# Thetis_RevF1_SCH.net
KiCad netlist of a schematic drawn in EAGLE
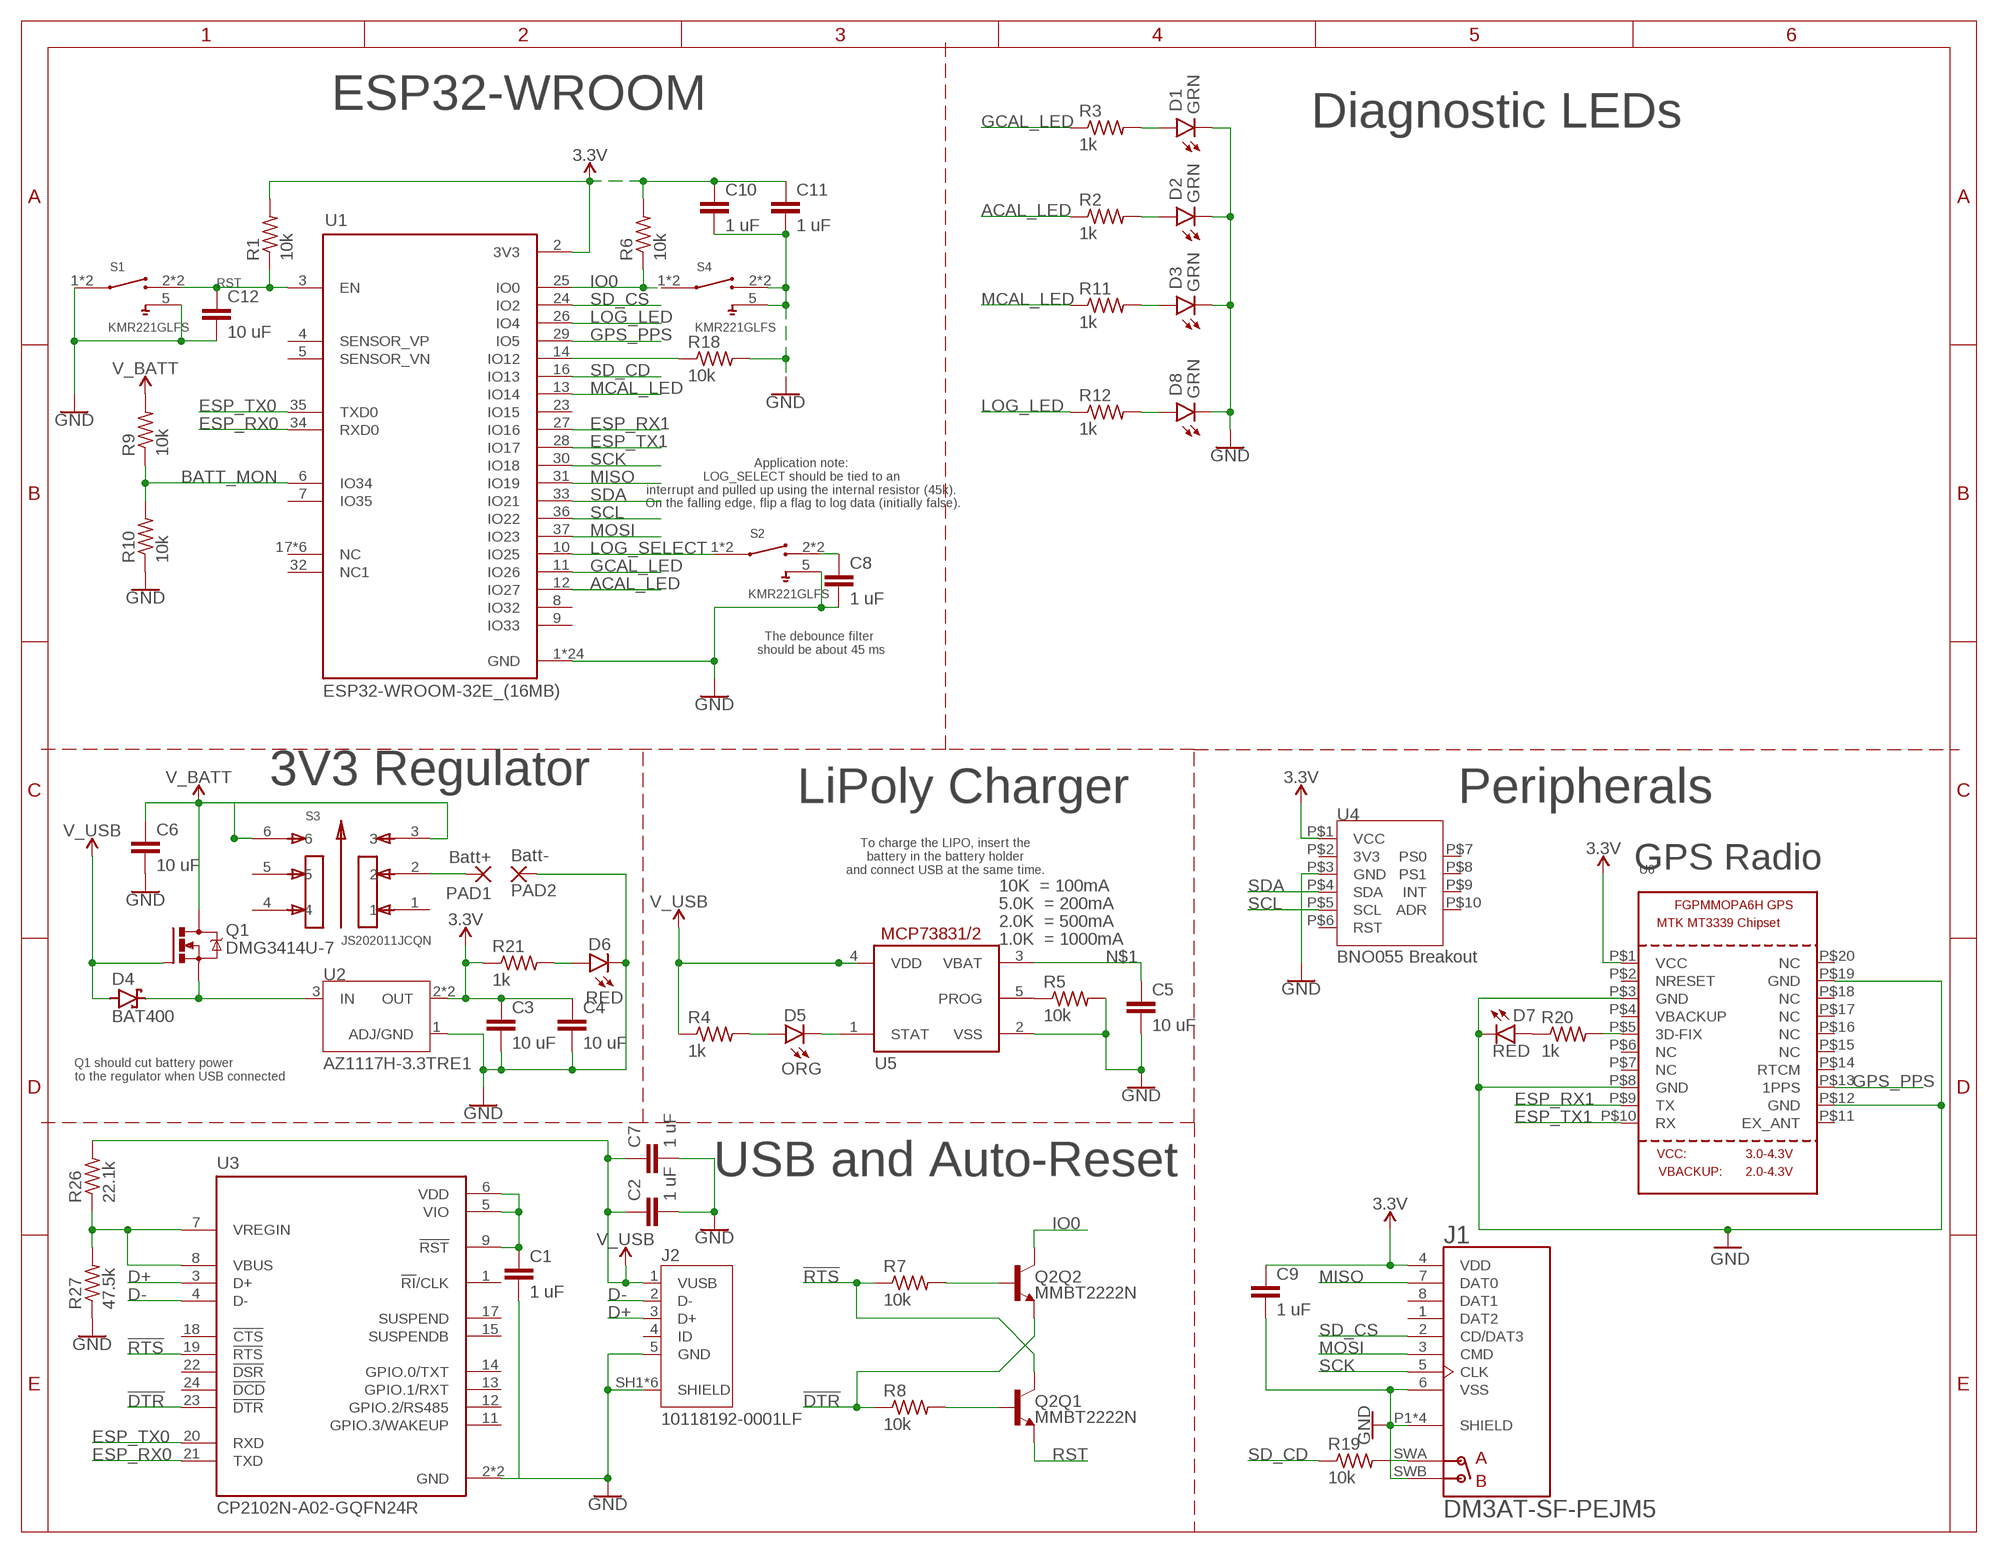
[diagram p0: schematic, sheet 1]

(export (version "E")
  (design (tool "Eeschema 10.0.6"))
  (components
    (comp (ref "C1")
      (value "1 uF")
      (footprint "eagle-import:C0603")
      (libsource (lib "eagle-import") (part "C-EUC0603"))
    )
    (comp (ref "C2")
      (value "1 uF")
      (footprint "eagle-import:C0603")
      (libsource (lib "eagle-import") (part "C-EUC0603"))
    )
    (comp (ref "C3")
      (value "10 uF")
      (footprint "eagle-import:C0603")
      (libsource (lib "eagle-import") (part "C-EUC0603"))
    )
    (comp (ref "C4")
      (value "10 uF")
      (footprint "eagle-import:C0603")
      (libsource (lib "eagle-import") (part "C-EUC0603"))
    )
    (comp (ref "C5")
      (value "10 uF")
      (footprint "eagle-import:C0603")
      (libsource (lib "eagle-import") (part "C-EUC0603"))
    )
    (comp (ref "C6")
      (value "10 uF")
      (footprint "eagle-import:C0603")
      (libsource (lib "eagle-import") (part "C-EUC0603"))
    )
    (comp (ref "C7")
      (value "1 uF")
      (footprint "eagle-import:C0603")
      (libsource (lib "eagle-import") (part "C-EUC0603"))
    )
    (comp (ref "C8")
      (value "1 uF")
      (footprint "eagle-import:C0603")
      (libsource (lib "eagle-import") (part "C-EUC0603"))
    )
    (comp (ref "C9")
      (value "1 uF")
      (footprint "eagle-import:C0603")
      (libsource (lib "eagle-import") (part "C-EUC0603"))
    )
    (comp (ref "C10")
      (value "1 uF")
      (footprint "eagle-import:C0603")
      (libsource (lib "eagle-import") (part "C-EUC0603"))
    )
    (comp (ref "C11")
      (value "1 uF")
      (footprint "eagle-import:C0603")
      (libsource (lib "eagle-import") (part "C-EUC0603"))
    )
    (comp (ref "C12")
      (value "10 uF")
      (footprint "eagle-import:C0603")
      (libsource (lib "eagle-import") (part "C-EUC0603"))
    )
    (comp (ref "D1")
      (value "GRN")
      (footprint "eagle-import:LEDC1608X65N")
      (libsource (lib "eagle-import") (part "CHIP-ROUND-G_0603"))
    )
    (comp (ref "D2")
      (value "GRN")
      (footprint "eagle-import:LEDC1608X65N")
      (libsource (lib "eagle-import") (part "CHIP-ROUND-G_0603"))
    )
    (comp (ref "D3")
      (value "GRN")
      (footprint "eagle-import:LEDC1608X65N")
      (libsource (lib "eagle-import") (part "CHIP-ROUND-G_0603"))
    )
    (comp (ref "D4")
      (value "BAT400")
      (footprint "eagle-import:SOT23")
      (libsource (lib "eagle-import") (part "BAS40"))
    )
    (comp (ref "D5")
      (value "ORG")
      (footprint "eagle-import:LEDC1608X65N")
      (libsource (lib "eagle-import") (part "CHIP-ROUND-G_0603"))
    )
    (comp (ref "D6")
      (value "RED")
      (footprint "eagle-import:LEDC1608X65N")
      (libsource (lib "eagle-import") (part "CHIP-ROUND-G_0603"))
    )
    (comp (ref "D7")
      (value "RED")
      (footprint "eagle-import:LEDC1608X35N")
      (libsource (lib "eagle-import") (part "CHIP-FLAT-Y_0603-0.35MM"))
    )
    (comp (ref "D8")
      (value "GRN")
      (footprint "eagle-import:LEDC1608X65N")
      (libsource (lib "eagle-import") (part "CHIP-ROUND-G_0603"))
    )
    (comp (ref "J1")
      (value "DM3AT-SF-PEJM5")
      (footprint "eagle-import:HRS_DM3AT-SF-PEJM5")
      (fields (field (name "MF") "Hirose"))
      (libsource (lib "eagle-import") (part "DM3AT-SF-PEJM5"))
    )
    (comp (ref "J2")
      (value "10118192-0001LF")
      (footprint "eagle-import:AMPHENOL_10118192-0001LF")
      (fields (field (name "MANUFACTURER") "Amphenol"))
      (libsource (lib "eagle-import") (part "10118192-0001LF"))
    )
    (comp (ref "PAD1")
      (value "Batt+")
      (footprint "eagle-import:SMD2,54-5,08")
      (libsource (lib "eagle-import") (part "SMD5"))
    )
    (comp (ref "PAD2")
      (value "Batt-")
      (footprint "eagle-import:SMD2,54-5,08")
      (libsource (lib "eagle-import") (part "SMD5"))
    )
    (comp (ref "Q1")
      (value "DMG3414U-7")
      (footprint "eagle-import:SOT23")
      (libsource (lib "eagle-import") (part "NMOSFETSOT23"))
    )
    (comp (ref "Q2")
      (value "MMBT2222N")
      (footprint "eagle-import:SC70-6")
      (libsource (lib "eagle-import") (part "TRANS_NPN_DUAL-MBT3904DW1T1"))
    )
    (comp (ref "R1")
      (value "10k")
      (footprint "eagle-import:R0603")
      (libsource (lib "eagle-import") (part "R-US_R0603"))
    )
    (comp (ref "R2")
      (value "1k")
      (footprint "eagle-import:R0603")
      (libsource (lib "eagle-import") (part "R-US_R0603"))
    )
    (comp (ref "R3")
      (value "1k")
      (footprint "eagle-import:R0603")
      (libsource (lib "eagle-import") (part "R-US_R0603"))
    )
    (comp (ref "R4")
      (value "1k")
      (footprint "eagle-import:R0603")
      (libsource (lib "eagle-import") (part "R-US_R0603"))
    )
    (comp (ref "R5")
      (value "10k")
      (footprint "eagle-import:R0603")
      (libsource (lib "eagle-import") (part "R-US_R0603"))
    )
    (comp (ref "R6")
      (value "10k")
      (footprint "eagle-import:R0603")
      (libsource (lib "eagle-import") (part "R-US_R0603"))
    )
    (comp (ref "R7")
      (value "10k")
      (footprint "eagle-import:R0603")
      (libsource (lib "eagle-import") (part "R-US_R0603"))
    )
    (comp (ref "R8")
      (value "10k")
      (footprint "eagle-import:R0603")
      (libsource (lib "eagle-import") (part "R-US_R0603"))
    )
    (comp (ref "R9")
      (value "10k")
      (footprint "eagle-import:R0603")
      (libsource (lib "eagle-import") (part "R-US_R0603"))
    )
    (comp (ref "R10")
      (value "10k")
      (footprint "eagle-import:R0603")
      (libsource (lib "eagle-import") (part "R-US_R0603"))
    )
    (comp (ref "R11")
      (value "1k")
      (footprint "eagle-import:R0603")
      (libsource (lib "eagle-import") (part "R-US_R0603"))
    )
    (comp (ref "R12")
      (value "1k")
      (footprint "eagle-import:R0603")
      (libsource (lib "eagle-import") (part "R-US_R0603"))
    )
    (comp (ref "R18")
      (value "10k")
      (footprint "eagle-import:R0603")
      (libsource (lib "eagle-import") (part "R-US_R0603"))
    )
    (comp (ref "R19")
      (value "10k")
      (footprint "eagle-import:R0603")
      (libsource (lib "eagle-import") (part "R-US_R0603"))
    )
    (comp (ref "R20")
      (value "1k")
      (footprint "eagle-import:R0603")
      (libsource (lib "eagle-import") (part "R-US_R0603"))
    )
    (comp (ref "R21")
      (value "1k")
      (footprint "eagle-import:R0603")
      (libsource (lib "eagle-import") (part "R-US_R0603"))
    )
    (comp (ref "R26")
      (value "22.1k")
      (footprint "eagle-import:R0603")
      (libsource (lib "eagle-import") (part "R-US_R0603"))
    )
    (comp (ref "R27")
      (value "47.5k")
      (footprint "eagle-import:R0603")
      (libsource (lib "eagle-import") (part "R-US_R0603"))
    )
    (comp (ref "S1")
      (value "KMR221GLFS")
      (footprint "eagle-import:SW_KMR221GLFS")
      (fields (field (name "MANUFACTURER") "CnK"))
      (libsource (lib "eagle-import") (part "KMR221GLFS"))
    )
    (comp (ref "S2")
      (value "KMR221GLFS")
      (footprint "eagle-import:SW_KMR221GLFS")
      (fields (field (name "MANUFACTURER") "CnK"))
      (libsource (lib "eagle-import") (part "KMR221GLFS"))
    )
    (comp (ref "S3")
      (value "JS202011JCQN")
      (footprint "eagle-import:SW_JS202011JCQN")
      (libsource (lib "eagle-import") (part "JS202011JCQN"))
    )
    (comp (ref "S4")
      (value "KMR221GLFS")
      (footprint "eagle-import:SW_KMR221GLFS")
      (fields (field (name "MANUFACTURER") "CnK"))
      (libsource (lib "eagle-import") (part "KMR221GLFS"))
    )
    (comp (ref "U1")
      (value "ESP32-WROOM-32E_(16MB)")
      (footprint "eagle-import:MODULE_ESP32-WROOM-32E_(16MB)")
      (fields (field (name "MANUFACTURER") "Espressif Systems"))
      (libsource (lib "eagle-import") (part "ESP32-WROOM-32E_(16MB)"))
    )
    (comp (ref "U2")
      (value "AZ1117H-3.3TRE1")
      (footprint "eagle-import:SOT230P700X180-4N")
      (fields (field (name "MF") "Diodes Inc.") (field (name "MP") "AZ1117EH-5.0TRG1"))
      (libsource (lib "eagle-import") (part "AZ1117EH-5.0TRG1"))
    )
    (comp (ref "U3")
      (value "CP2102N-A02-GQFN24R")
      (footprint "eagle-import:QFN50P400X400X80-25N")
      (fields (field (name "MANUFACTURER") "Silicon Labs"))
      (libsource (lib "eagle-import") (part "CP2102N-A02-GQFN24R"))
    )
    (comp (ref "U4")
      (value "BNO055 Breakout")
      (footprint "eagle-import:ADAFRUIT-BNO055-BREAKOUT-SMD")
      (libsource (lib "eagle-import") (part "ADAFRUIT-BNO055-BREAKOUT-SMD"))
    )
    (comp (ref "U5")
      (value "MCP73831/OT")
      (footprint "eagle-import:SOT23-5L")
      (libsource (lib "eagle-import") (part "MCP73831/OT"))
    )
    (comp (ref "U6")
      (value "GPS_FGPMMOPA6H")
      (footprint "eagle-import:FGPMMOPA6H")
      (libsource (lib "eagle-import") (part "GPS_FGPMMOPA6H"))
    )
  )
  (nets
    (net (code "1") (name "/3V3") (class "Default")
      (node (ref "U4") (pin "P$2") (pinfunction "3V3_P$2") (pintype "power_in"))
    )
    (net (code "2") (name "/ACAL_LED") (class "Default")
      (node (ref "R2") (pin "1") (pinfunction "1_1") (pintype "passive"))
      (node (ref "U1") (pin "12") (pinfunction "IO27_12") (pintype "bidirectional"))
    )
    (net (code "3") (name "/BATT_MON") (class "Default")
      (node (ref "R10") (pin "2") (pinfunction "2_2") (pintype "passive"))
      (node (ref "R9") (pin "1") (pinfunction "1_1") (pintype "passive"))
      (node (ref "U1") (pin "6") (pinfunction "IO34_6") (pintype "input"))
    )
    (net (code "4") (name "/D+") (class "Default")
      (node (ref "J2") (pin "3") (pinfunction "D+_3") (pintype "passive"))
      (node (ref "U3") (pin "3") (pinfunction "D+_3") (pintype "bidirectional"))
    )
    (net (code "5") (name "/D-") (class "Default")
      (node (ref "J2") (pin "2") (pinfunction "D-_2") (pintype "passive"))
      (node (ref "U3") (pin "4") (pinfunction "D-_4") (pintype "bidirectional"))
    )
    (net (code "6") (name "/ESP_RX0") (class "Default")
      (node (ref "U1") (pin "34") (pinfunction "RXD0_34") (pintype "bidirectional"))
      (node (ref "U3") (pin "21") (pinfunction "TXD_21") (pintype "output"))
    )
    (net (code "7") (name "/ESP_RX1") (class "Default")
      (node (ref "U1") (pin "27") (pinfunction "IO16_27") (pintype "bidirectional"))
      (node (ref "U6") (pin "P$9") (pinfunction "TX_P$9") (pintype "bidirectional"))
    )
    (net (code "8") (name "/ESP_TX0") (class "Default")
      (node (ref "U1") (pin "35") (pinfunction "TXD0_35") (pintype "bidirectional"))
      (node (ref "U3") (pin "20") (pinfunction "RXD_20") (pintype "input"))
    )
    (net (code "9") (name "/ESP_TX1") (class "Default")
      (node (ref "U1") (pin "28") (pinfunction "IO17_28") (pintype "bidirectional"))
      (node (ref "U6") (pin "P$10") (pinfunction "RX_P$10") (pintype "bidirectional"))
    )
    (net (code "10") (name "/GCAL_LED") (class "Default")
      (node (ref "R3") (pin "1") (pinfunction "1_1") (pintype "passive"))
      (node (ref "U1") (pin "11") (pinfunction "IO26_11") (pintype "bidirectional"))
    )
    (net (code "11") (name "/GPS_PPS") (class "Default")
      (node (ref "U1") (pin "29") (pinfunction "IO5_29") (pintype "bidirectional"))
      (node (ref "U6") (pin "P$13") (pinfunction "1PPS_P$13") (pintype "bidirectional"))
    )
    (net (code "12") (name "/IO0") (class "Default")
      (node (ref "Q2") (pin "6") (pinfunction "C_6") (pintype "passive"))
      (node (ref "R6") (pin "1") (pinfunction "1_1") (pintype "passive"))
      (node (ref "S4") (pin "1") (pinfunction "1_1") (pintype "passive"))
      (node (ref "S4") (pin "4") (pinfunction "1_4") (pintype "passive"))
      (node (ref "U1") (pin "25") (pinfunction "IO0_25") (pintype "bidirectional"))
    )
    (net (code "13") (name "/LOG_LED") (class "Default")
      (node (ref "R12") (pin "1") (pinfunction "1_1") (pintype "passive"))
      (node (ref "U1") (pin "26") (pinfunction "IO4_26") (pintype "bidirectional"))
    )
    (net (code "14") (name "/LOG_SELECT") (class "Default")
      (node (ref "S2") (pin "1") (pinfunction "1_1") (pintype "passive"))
      (node (ref "S2") (pin "4") (pinfunction "1_4") (pintype "passive"))
      (node (ref "U1") (pin "10") (pinfunction "IO25_10") (pintype "bidirectional"))
    )
    (net (code "15") (name "/MCAL_LED") (class "Default")
      (node (ref "R11") (pin "1") (pinfunction "1_1") (pintype "passive"))
      (node (ref "U1") (pin "13") (pinfunction "IO14_13") (pintype "bidirectional"))
    )
    (net (code "16") (name "/MISO") (class "Default")
      (node (ref "J1") (pin "7") (pinfunction "DAT0_7") (pintype "bidirectional"))
      (node (ref "U1") (pin "31") (pinfunction "IO19_31") (pintype "bidirectional"))
    )
    (net (code "17") (name "/MOSI") (class "Default")
      (node (ref "J1") (pin "3") (pinfunction "CMD_3") (pintype "bidirectional"))
      (node (ref "U1") (pin "37") (pinfunction "IO23_37") (pintype "bidirectional"))
    )
    (net (code "18") (name "/N$1") (class "Default")
      (node (ref "C5") (pin "1") (pinfunction "1_1") (pintype "passive"))
      (node (ref "PAD1") (pin "1") (pinfunction "P_1") (pintype "passive"))
      (node (ref "S3") (pin "2") (pinfunction "2_2") (pintype "passive"))
      (node (ref "U5") (pin "3") (pinfunction "VBAT_3") (pintype "bidirectional"))
    )
    (net (code "19") (name "/RST") (class "Default")
      (node (ref "C12") (pin "1") (pinfunction "1_1") (pintype "passive"))
      (node (ref "Q2") (pin "4") (pinfunction "E_4") (pintype "passive"))
      (node (ref "R1") (pin "1") (pinfunction "1_1") (pintype "passive"))
      (node (ref "S1") (pin "2") (pinfunction "3_2") (pintype "passive"))
      (node (ref "S1") (pin "3") (pinfunction "3_3") (pintype "passive"))
      (node (ref "U1") (pin "3") (pinfunction "EN_3") (pintype "input"))
    )
    (net (code "20") (name "/SCK") (class "Default")
      (node (ref "J1") (pin "5") (pinfunction "CLK_5") (pintype "bidirectional"))
      (node (ref "U1") (pin "30") (pinfunction "IO18_30") (pintype "bidirectional"))
    )
    (net (code "21") (name "/SCL") (class "Default")
      (node (ref "U1") (pin "36") (pinfunction "IO22_36") (pintype "bidirectional"))
      (node (ref "U4") (pin "P$5") (pinfunction "SCL_P$5") (pintype "bidirectional"))
    )
    (net (code "22") (name "/SDA") (class "Default")
      (node (ref "U1") (pin "33") (pinfunction "IO21_33") (pintype "bidirectional"))
      (node (ref "U4") (pin "P$4") (pinfunction "SDA_P$4") (pintype "bidirectional"))
    )
    (net (code "23") (name "/SD_CD") (class "Default")
      (node (ref "R19") (pin "1") (pinfunction "1_1") (pintype "passive"))
      (node (ref "U1") (pin "16") (pinfunction "IO13_16") (pintype "bidirectional"))
    )
    (net (code "24") (name "/SD_CS") (class "Default")
      (node (ref "J1") (pin "2") (pinfunction "CD/DAT3_2") (pintype "bidirectional"))
      (node (ref "U1") (pin "24") (pinfunction "IO2_24") (pintype "bidirectional"))
    )
    (net (code "25") (name "/~{DTR}") (class "Default")
      (node (ref "Q2") (pin "1") (pinfunction "E_1") (pintype "passive"))
      (node (ref "R8") (pin "1") (pinfunction "1_1") (pintype "passive"))
      (node (ref "U3") (pin "23") (pinfunction "~{DTR}_23") (pintype "output"))
    )
    (net (code "26") (name "/~{RTS}") (class "Default")
      (node (ref "Q2") (pin "3") (pinfunction "C_3") (pintype "passive"))
      (node (ref "R7") (pin "1") (pinfunction "1_1") (pintype "passive"))
      (node (ref "U3") (pin "19") (pinfunction "~{RTS}_19") (pintype "output"))
    )
    (net (code "27") (name "3.3V") (class "Default")
      (node (ref "C10") (pin "1") (pinfunction "1_1") (pintype "passive"))
      (node (ref "C11") (pin "1") (pinfunction "1_1") (pintype "passive"))
      (node (ref "C3") (pin "1") (pinfunction "1_1") (pintype "passive"))
      (node (ref "C4") (pin "1") (pinfunction "1_1") (pintype "passive"))
      (node (ref "C9") (pin "1") (pinfunction "1_1") (pintype "passive"))
      (node (ref "J1") (pin "4") (pinfunction "VDD_4") (pintype "power_in"))
      (node (ref "R1") (pin "2") (pinfunction "2_2") (pintype "passive"))
      (node (ref "R21") (pin "1") (pinfunction "1_1") (pintype "passive"))
      (node (ref "R6") (pin "2") (pinfunction "2_2") (pintype "passive"))
      (node (ref "U1") (pin "2") (pinfunction "3V3_2") (pintype "power_in"))
      (node (ref "U2") (pin "2") (pinfunction "OUT_2") (pintype "output"))
      (node (ref "U2") (pin "4") (pinfunction "OUT_4") (pintype "output"))
      (node (ref "U4") (pin "P$1") (pinfunction "VCC_P$1") (pintype "power_in"))
      (node (ref "U6") (pin "P$1") (pinfunction "VCC_P$1") (pintype "bidirectional"))
    )
    (net (code "28") (name "GND") (class "Default")
      (node (ref "C1") (pin "2") (pinfunction "2_2") (pintype "passive"))
      (node (ref "C10") (pin "2") (pinfunction "2_2") (pintype "passive"))
      (node (ref "C11") (pin "2") (pinfunction "2_2") (pintype "passive"))
      (node (ref "C12") (pin "2") (pinfunction "2_2") (pintype "passive"))
      (node (ref "C2") (pin "2") (pinfunction "2_2") (pintype "passive"))
      (node (ref "C3") (pin "2") (pinfunction "2_2") (pintype "passive"))
      (node (ref "C4") (pin "2") (pinfunction "2_2") (pintype "passive"))
      (node (ref "C5") (pin "2") (pinfunction "2_2") (pintype "passive"))
      (node (ref "C6") (pin "2") (pinfunction "2_2") (pintype "passive"))
      (node (ref "C7") (pin "2") (pinfunction "2_2") (pintype "passive"))
      (node (ref "C8") (pin "2") (pinfunction "2_2") (pintype "passive"))
      (node (ref "C9") (pin "2") (pinfunction "2_2") (pintype "passive"))
      (node (ref "D1") (pin "C") (pinfunction "C_C") (pintype "passive"))
      (node (ref "D2") (pin "C") (pinfunction "C_C") (pintype "passive"))
      (node (ref "D3") (pin "C") (pinfunction "C_C") (pintype "passive"))
      (node (ref "D6") (pin "C") (pinfunction "C_C") (pintype "passive"))
      (node (ref "D7") (pin "C") (pinfunction "C_C") (pintype "passive"))
      (node (ref "D8") (pin "C") (pinfunction "C_C") (pintype "passive"))
      (node (ref "J1") (pin "6") (pinfunction "VSS_6") (pintype "power_in"))
      (node (ref "J1") (pin "P1") (pinfunction "SHIELD_P1") (pintype "passive"))
      (node (ref "J1") (pin "P2") (pinfunction "SHIELD_P2") (pintype "passive"))
      (node (ref "J1") (pin "P3") (pinfunction "SHIELD_P3") (pintype "passive"))
      (node (ref "J1") (pin "P4") (pinfunction "SHIELD_P4") (pintype "passive"))
      (node (ref "J1") (pin "SWB") (pinfunction "B_SWB") (pintype "bidirectional"))
      (node (ref "J2") (pin "5") (pinfunction "GND_5") (pintype "passive"))
      (node (ref "J2") (pin "SH1") (pinfunction "SHIELD_SH1") (pintype "passive"))
      (node (ref "J2") (pin "SH2") (pinfunction "SHIELD_SH2") (pintype "passive"))
      (node (ref "J2") (pin "SH3") (pinfunction "SHIELD_SH3") (pintype "passive"))
      (node (ref "J2") (pin "SH4") (pinfunction "SHIELD_SH4") (pintype "passive"))
      (node (ref "J2") (pin "SH5") (pinfunction "SHIELD_SH5") (pintype "passive"))
      (node (ref "J2") (pin "SH6") (pinfunction "SHIELD_SH6") (pintype "passive"))
      (node (ref "PAD2") (pin "1") (pinfunction "P_1") (pintype "passive"))
      (node (ref "R10") (pin "1") (pinfunction "1_1") (pintype "passive"))
      (node (ref "R18") (pin "2") (pinfunction "2_2") (pintype "passive"))
      (node (ref "R27") (pin "1") (pinfunction "1_1") (pintype "passive"))
      (node (ref "R5") (pin "2") (pinfunction "2_2") (pintype "passive"))
      (node (ref "S1") (pin "1") (pinfunction "1_1") (pintype "passive"))
      (node (ref "S1") (pin "4") (pinfunction "1_4") (pintype "passive"))
      (node (ref "S1") (pin "5") (pinfunction "5_5") (pintype "passive"))
      (node (ref "S2") (pin "5") (pinfunction "5_5") (pintype "passive"))
      (node (ref "S4") (pin "2") (pinfunction "3_2") (pintype "passive"))
      (node (ref "S4") (pin "3") (pinfunction "3_3") (pintype "passive"))
      (node (ref "S4") (pin "5") (pinfunction "5_5") (pintype "passive"))
      (node (ref "U1") (pin "1") (pinfunction "GND_1") (pintype "power_in"))
      (node (ref "U1") (pin "15") (pinfunction "GND_15") (pintype "power_in"))
      (node (ref "U1") (pin "38") (pinfunction "GND_38") (pintype "power_in"))
      (node (ref "U1") (pin "39_1") (pinfunction "GND_39_1") (pintype "power_in"))
      (node (ref "U1") (pin "39_10") (pinfunction "GND_39_10") (pintype "power_in"))
      (node (ref "U1") (pin "39_11") (pinfunction "GND_39_11") (pintype "power_in"))
      (node (ref "U1") (pin "39_12") (pinfunction "GND_39_12") (pintype "power_in"))
      (node (ref "U1") (pin "39_13") (pinfunction "GND_39_13") (pintype "power_in"))
      (node (ref "U1") (pin "39_14") (pinfunction "GND_39_14") (pintype "power_in"))
      (node (ref "U1") (pin "39_15") (pinfunction "GND_39_15") (pintype "power_in"))
      (node (ref "U1") (pin "39_16") (pinfunction "GND_39_16") (pintype "power_in"))
      (node (ref "U1") (pin "39_17") (pinfunction "GND_39_17") (pintype "power_in"))
      (node (ref "U1") (pin "39_18") (pinfunction "GND_39_18") (pintype "power_in"))
      (node (ref "U1") (pin "39_19") (pinfunction "GND_39_19") (pintype "power_in"))
      (node (ref "U1") (pin "39_2") (pinfunction "GND_39_2") (pintype "power_in"))
      (node (ref "U1") (pin "39_20") (pinfunction "GND_39_20") (pintype "power_in"))
      (node (ref "U1") (pin "39_21") (pinfunction "GND_39_21") (pintype "power_in"))
      (node (ref "U1") (pin "39_3") (pinfunction "GND_39_3") (pintype "power_in"))
      (node (ref "U1") (pin "39_4") (pinfunction "GND_39_4") (pintype "power_in"))
      (node (ref "U1") (pin "39_5") (pinfunction "GND_39_5") (pintype "power_in"))
      (node (ref "U1") (pin "39_6") (pinfunction "GND_39_6") (pintype "power_in"))
      (node (ref "U1") (pin "39_7") (pinfunction "GND_39_7") (pintype "power_in"))
      (node (ref "U1") (pin "39_8") (pinfunction "GND_39_8") (pintype "power_in"))
      (node (ref "U1") (pin "39_9") (pinfunction "GND_39_9") (pintype "power_in"))
      (node (ref "U2") (pin "1") (pinfunction "ADJ/GND_1") (pintype "power_in"))
      (node (ref "U3") (pin "2") (pinfunction "GND_2") (pintype "power_in"))
      (node (ref "U3") (pin "25") (pinfunction "GND_25") (pintype "power_in"))
      (node (ref "U4") (pin "P$3") (pinfunction "GND_P$3") (pintype "power_in"))
      (node (ref "U5") (pin "2") (pinfunction "VSS_2") (pintype "power_in"))
      (node (ref "U6") (pin "P$12") (pinfunction "GND_P$12") (pintype "bidirectional"))
      (node (ref "U6") (pin "P$19") (pinfunction "GND_P$19") (pintype "bidirectional"))
      (node (ref "U6") (pin "P$3") (pinfunction "GND_P$3") (pintype "bidirectional"))
      (node (ref "U6") (pin "P$8") (pinfunction "GND_P$8") (pintype "bidirectional"))
    )
    (net (code "29") (name "Net-(C8-Pad1)") (class "Default")
      (node (ref "C8") (pin "1") (pinfunction "1_1") (pintype "passive"))
      (node (ref "S2") (pin "2") (pinfunction "3_2") (pintype "passive"))
      (node (ref "S2") (pin "3") (pinfunction "3_3") (pintype "passive"))
    )
    (net (code "30") (name "Net-(D1-PadA)") (class "Default")
      (node (ref "D1") (pin "A") (pinfunction "A_A") (pintype "passive"))
      (node (ref "R3") (pin "2") (pinfunction "2_2") (pintype "passive"))
    )
    (net (code "31") (name "Net-(D2-PadA)") (class "Default")
      (node (ref "D2") (pin "A") (pinfunction "A_A") (pintype "passive"))
      (node (ref "R2") (pin "2") (pinfunction "2_2") (pintype "passive"))
    )
    (net (code "32") (name "Net-(D3-PadA)") (class "Default")
      (node (ref "D3") (pin "A") (pinfunction "A_A") (pintype "passive"))
      (node (ref "R11") (pin "2") (pinfunction "2_2") (pintype "passive"))
    )
    (net (code "33") (name "Net-(D4-C)") (class "Default")
      (node (ref "D4") (pin "3") (pinfunction "C_3") (pintype "passive"))
      (node (ref "Q1") (pin "2") (pinfunction "S_2") (pintype "passive"))
      (node (ref "U2") (pin "3") (pinfunction "IN_3") (pintype "input"))
    )
    (net (code "34") (name "Net-(D5-PadA)") (class "Default")
      (node (ref "D5") (pin "A") (pinfunction "A_A") (pintype "passive"))
      (node (ref "R4") (pin "2") (pinfunction "2_2") (pintype "passive"))
    )
    (net (code "35") (name "Net-(D6-PadA)") (class "Default")
      (node (ref "D6") (pin "A") (pinfunction "A_A") (pintype "passive"))
      (node (ref "R21") (pin "2") (pinfunction "2_2") (pintype "passive"))
    )
    (net (code "36") (name "Net-(D7-PadA)") (class "Default")
      (node (ref "D7") (pin "A") (pinfunction "A_A") (pintype "passive"))
      (node (ref "R20") (pin "1") (pinfunction "1_1") (pintype "passive"))
    )
    (net (code "37") (name "Net-(D8-PadA)") (class "Default")
      (node (ref "D8") (pin "A") (pinfunction "A_A") (pintype "passive"))
      (node (ref "R12") (pin "2") (pinfunction "2_2") (pintype "passive"))
    )
    (net (code "38") (name "Net-(J1-A)") (class "Default")
      (node (ref "J1") (pin "SWA") (pinfunction "A_SWA") (pintype "bidirectional"))
      (node (ref "R19") (pin "2") (pinfunction "2_2") (pintype "passive"))
    )
    (net (code "39") (name "Net-(Q2A-B)") (class "Default")
      (node (ref "Q2") (pin "5") (pinfunction "B_5") (pintype "passive"))
      (node (ref "R8") (pin "2") (pinfunction "2_2") (pintype "passive"))
    )
    (net (code "40") (name "Net-(Q2B-B)") (class "Default")
      (node (ref "Q2") (pin "2") (pinfunction "B_2") (pintype "passive"))
      (node (ref "R7") (pin "2") (pinfunction "2_2") (pintype "passive"))
    )
    (net (code "41") (name "Net-(U1-IO12)") (class "Default")
      (node (ref "R18") (pin "1") (pinfunction "1_1") (pintype "passive"))
      (node (ref "U1") (pin "14") (pinfunction "IO12_14") (pintype "bidirectional"))
    )
    (net (code "42") (name "Net-(U3-VBUS)") (class "Default")
      (node (ref "R26") (pin "1") (pinfunction "1_1") (pintype "passive"))
      (node (ref "R27") (pin "2") (pinfunction "2_2") (pintype "passive"))
      (node (ref "U3") (pin "7") (pinfunction "VREGIN_7") (pintype "input"))
      (node (ref "U3") (pin "8") (pinfunction "VBUS_8") (pintype "input"))
    )
    (net (code "43") (name "Net-(U3-VDD)") (class "Default")
      (node (ref "C1") (pin "1") (pinfunction "1_1") (pintype "passive"))
      (node (ref "U3") (pin "5") (pinfunction "VIO_5") (pintype "power_in"))
      (node (ref "U3") (pin "6") (pinfunction "VDD_6") (pintype "power_in"))
      (node (ref "U3") (pin "9") (pinfunction "~{RST}_9") (pintype "bidirectional"))
    )
    (net (code "44") (name "Net-(U5-PROG)") (class "Default")
      (node (ref "R5") (pin "1") (pinfunction "1_1") (pintype "passive"))
      (node (ref "U5") (pin "5") (pinfunction "PROG_5") (pintype "input"))
    )
    (net (code "45") (name "Net-(U5-STAT)") (class "Default")
      (node (ref "D5") (pin "C") (pinfunction "C_C") (pintype "passive"))
      (node (ref "U5") (pin "1") (pinfunction "STAT_1") (pintype "output"))
    )
    (net (code "46") (name "Net-(U6-3D-FIX)") (class "Default")
      (node (ref "R20") (pin "2") (pinfunction "2_2") (pintype "passive"))
      (node (ref "U6") (pin "P$5") (pinfunction "3D-FIX_P$5") (pintype "bidirectional"))
    )
    (net (code "47") (name "V_BATT") (class "Default")
      (node (ref "C6") (pin "1") (pinfunction "1_1") (pintype "passive"))
      (node (ref "Q1") (pin "3") (pinfunction "D_3") (pintype "passive"))
      (node (ref "R9") (pin "2") (pinfunction "2_2") (pintype "passive"))
      (node (ref "S3") (pin "3") (pinfunction "3_3") (pintype "passive"))
      (node (ref "S3") (pin "6") (pinfunction "6_6") (pintype "passive"))
    )
    (net (code "48") (name "V_USB") (class "Default")
      (node (ref "C2") (pin "1") (pinfunction "1_1") (pintype "passive"))
      (node (ref "C7") (pin "1") (pinfunction "1_1") (pintype "passive"))
      (node (ref "D4") (pin "1") (pinfunction "A_1") (pintype "passive"))
      (node (ref "J2") (pin "1") (pinfunction "VUSB_1") (pintype "passive"))
      (node (ref "Q1") (pin "1") (pinfunction "G_1") (pintype "passive"))
      (node (ref "R26") (pin "2") (pinfunction "2_2") (pintype "passive"))
      (node (ref "R4") (pin "1") (pinfunction "1_1") (pintype "passive"))
      (node (ref "U5") (pin "4") (pinfunction "VDD_4") (pintype "power_in"))
    )
    (net (code "49") (name "unconnected-(J1-DAT1-Pad8)") (class "Default")
      (node (ref "J1") (pin "8") (pinfunction "DAT1_8") (pintype "bidirectional"))
    )
    (net (code "50") (name "unconnected-(J1-DAT2-Pad1)") (class "Default")
      (node (ref "J1") (pin "1") (pinfunction "DAT2_1") (pintype "bidirectional"))
    )
    (net (code "51") (name "unconnected-(J2-ID-Pad4)") (class "Default")
      (node (ref "J2") (pin "4") (pinfunction "ID_4") (pintype "passive"))
    )
    (net (code "52") (name "unconnected-(S3-Pad1)") (class "Default")
      (node (ref "S3") (pin "1") (pinfunction "1_1") (pintype "passive"))
    )
    (net (code "53") (name "unconnected-(S3-Pad4)") (class "Default")
      (node (ref "S3") (pin "4") (pinfunction "4_4") (pintype "passive"))
    )
    (net (code "54") (name "unconnected-(S3-Pad5)") (class "Default")
      (node (ref "S3") (pin "5") (pinfunction "5_5") (pintype "passive"))
    )
    (net (code "55") (name "unconnected-(U1-IO15-Pad23)") (class "Default")
      (node (ref "U1") (pin "23") (pinfunction "IO15_23") (pintype "bidirectional"))
    )
    (net (code "56") (name "unconnected-(U1-IO32-Pad8)") (class "Default")
      (node (ref "U1") (pin "8") (pinfunction "IO32_8") (pintype "bidirectional"))
    )
    (net (code "57") (name "unconnected-(U1-IO33-Pad9)") (class "Default")
      (node (ref "U1") (pin "9") (pinfunction "IO33_9") (pintype "bidirectional"))
    )
    (net (code "58") (name "unconnected-(U1-IO35-Pad7)") (class "Default")
      (node (ref "U1") (pin "7") (pinfunction "IO35_7") (pintype "input"))
    )
    (net (code "59") (name "unconnected-(U1-NC-Pad17)") (class "Default")
      (node (ref "U1") (pin "17") (pinfunction "NC_17") (pintype "no_connect"))
    )
    (net (code "60") (name "unconnected-(U1-NC-Pad18)") (class "Default")
      (node (ref "U1") (pin "18") (pinfunction "NC_18") (pintype "no_connect"))
    )
    (net (code "61") (name "unconnected-(U1-NC-Pad19)") (class "Default")
      (node (ref "U1") (pin "19") (pinfunction "NC_19") (pintype "no_connect"))
    )
    (net (code "62") (name "unconnected-(U1-NC-Pad20)") (class "Default")
      (node (ref "U1") (pin "20") (pinfunction "NC_20") (pintype "no_connect"))
    )
    (net (code "63") (name "unconnected-(U1-NC-Pad21)") (class "Default")
      (node (ref "U1") (pin "21") (pinfunction "NC_21") (pintype "no_connect"))
    )
    (net (code "64") (name "unconnected-(U1-NC-Pad22)") (class "Default")
      (node (ref "U1") (pin "22") (pinfunction "NC_22") (pintype "no_connect"))
    )
    (net (code "65") (name "unconnected-(U1-NC1-Pad32)") (class "Default")
      (node (ref "U1") (pin "32") (pinfunction "NC1_32") (pintype "no_connect"))
    )
    (net (code "66") (name "unconnected-(U1-SENSOR_VN-Pad5)") (class "Default")
      (node (ref "U1") (pin "5") (pinfunction "SENSOR_VN_5") (pintype "input"))
    )
    (net (code "67") (name "unconnected-(U1-SENSOR_VP-Pad4)") (class "Default")
      (node (ref "U1") (pin "4") (pinfunction "SENSOR_VP_4") (pintype "input"))
    )
    (net (code "68") (name "unconnected-(U3-GPIO.0{slash}TXT-Pad14)") (class "Default")
      (node (ref "U3") (pin "14") (pinfunction "GPIO.0/TXT_14") (pintype "bidirectional"))
    )
    (net (code "69") (name "unconnected-(U3-GPIO.1{slash}RXT-Pad13)") (class "Default")
      (node (ref "U3") (pin "13") (pinfunction "GPIO.1/RXT_13") (pintype "bidirectional"))
    )
    (net (code "70") (name "unconnected-(U3-GPIO.2{slash}RS485-Pad12)") (class "Default")
      (node (ref "U3") (pin "12") (pinfunction "GPIO.2/RS485_12") (pintype "bidirectional"))
    )
    (net (code "71") (name "unconnected-(U3-GPIO.3{slash}WAKEUP-Pad11)") (class "Default")
      (node (ref "U3") (pin "11") (pinfunction "GPIO.3/WAKEUP_11") (pintype "bidirectional"))
    )
    (net (code "72") (name "unconnected-(U3-SUSPEND-Pad17)") (class "Default")
      (node (ref "U3") (pin "17") (pinfunction "SUSPEND_17") (pintype "output"))
    )
    (net (code "73") (name "unconnected-(U3-SUSPENDB-Pad15)") (class "Default")
      (node (ref "U3") (pin "15") (pinfunction "SUSPENDB_15") (pintype "output"))
    )
    (net (code "74") (name "unconnected-(U3-~{CTS}-Pad18)") (class "Default")
      (node (ref "U3") (pin "18") (pinfunction "~{CTS}_18") (pintype "input"))
    )
    (net (code "75") (name "unconnected-(U3-~{DCD}-Pad24)") (class "Default")
      (node (ref "U3") (pin "24") (pinfunction "~{DCD}_24") (pintype "input"))
    )
    (net (code "76") (name "unconnected-(U3-~{DSR}-Pad22)") (class "Default")
      (node (ref "U3") (pin "22") (pinfunction "~{DSR}_22") (pintype "input"))
    )
    (net (code "77") (name "unconnected-(U3-~{RI}{slash}CLK-Pad1)") (class "Default")
      (node (ref "U3") (pin "1") (pinfunction "~{RI}/CLK_1") (pintype "bidirectional"))
    )
    (net (code "78") (name "unconnected-(U4-ADR-PadP$10)") (class "Default")
      (node (ref "U4") (pin "P$10") (pinfunction "ADR_P$10") (pintype "bidirectional"))
    )
    (net (code "79") (name "unconnected-(U4-INT-PadP$9)") (class "Default")
      (node (ref "U4") (pin "P$9") (pinfunction "INT_P$9") (pintype "bidirectional"))
    )
    (net (code "80") (name "unconnected-(U4-PS0-PadP$7)") (class "Default")
      (node (ref "U4") (pin "P$7") (pinfunction "PS0_P$7") (pintype "bidirectional"))
    )
    (net (code "81") (name "unconnected-(U4-PS1-PadP$8)") (class "Default")
      (node (ref "U4") (pin "P$8") (pinfunction "PS1_P$8") (pintype "bidirectional"))
    )
    (net (code "82") (name "unconnected-(U4-RST-PadP$6)") (class "Default")
      (node (ref "U4") (pin "P$6") (pinfunction "RST_P$6") (pintype "input"))
    )
    (net (code "83") (name "unconnected-(U6-EX_ANT-PadP$11)") (class "Default")
      (node (ref "U6") (pin "P$11") (pinfunction "EX_ANT_P$11") (pintype "bidirectional"))
    )
    (net (code "84") (name "unconnected-(U6-NC-PadP$6)") (class "Default")
      (node (ref "U6") (pin "P$6") (pinfunction "NC_P$6") (pintype "bidirectional"))
    )
    (net (code "85") (name "unconnected-(U6-NC-PadP$7)") (class "Default")
      (node (ref "U6") (pin "P$7") (pinfunction "NC_P$7") (pintype "bidirectional"))
    )
    (net (code "86") (name "unconnected-(U6-NC-PadP$15)") (class "Default")
      (node (ref "U6") (pin "P$15") (pinfunction "NC_P$15") (pintype "bidirectional"))
    )
    (net (code "87") (name "unconnected-(U6-NC-PadP$16)") (class "Default")
      (node (ref "U6") (pin "P$16") (pinfunction "NC_P$16") (pintype "bidirectional"))
    )
    (net (code "88") (name "unconnected-(U6-NC-PadP$17)") (class "Default")
      (node (ref "U6") (pin "P$17") (pinfunction "NC_P$17") (pintype "bidirectional"))
    )
    (net (code "89") (name "unconnected-(U6-NC-PadP$18)") (class "Default")
      (node (ref "U6") (pin "P$18") (pinfunction "NC_P$18") (pintype "bidirectional"))
    )
    (net (code "90") (name "unconnected-(U6-NC-PadP$20)") (class "Default")
      (node (ref "U6") (pin "P$20") (pinfunction "NC_P$20") (pintype "bidirectional"))
    )
    (net (code "91") (name "unconnected-(U6-NRESET-PadP$2)") (class "Default")
      (node (ref "U6") (pin "P$2") (pinfunction "NRESET_P$2") (pintype "bidirectional"))
    )
    (net (code "92") (name "unconnected-(U6-RTCM-PadP$14)") (class "Default")
      (node (ref "U6") (pin "P$14") (pinfunction "RTCM_P$14") (pintype "bidirectional"))
    )
    (net (code "93") (name "unconnected-(U6-VBACKUP-PadP$4)") (class "Default")
      (node (ref "U6") (pin "P$4") (pinfunction "VBACKUP_P$4") (pintype "bidirectional"))
    )
  )
)
